# power.net
KiCad netlist of a schematic drawn in Altium Designer
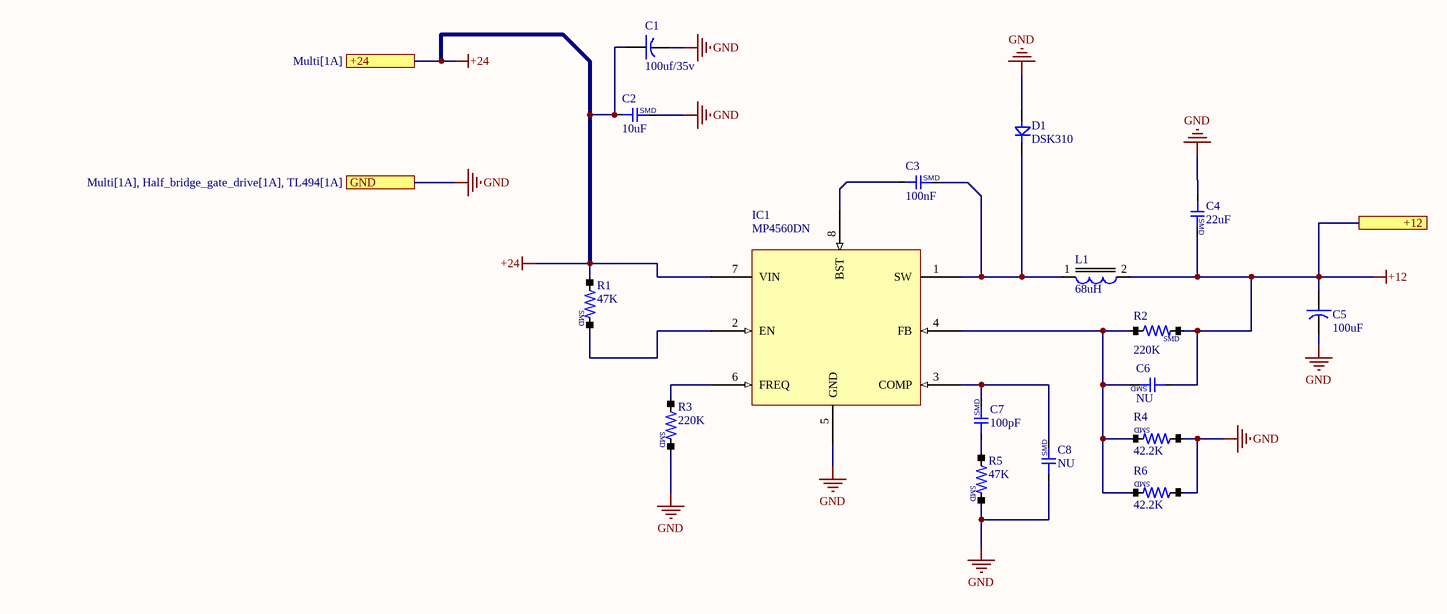
[diagram p0: power.SchDoc]

(export (version "E")
  (design (tool "Eeschema 10.0.6"))
  (components
    (comp (ref "C1")
      (value "100uf/35v")
      (footprint "cap/330u/16v")
      (libsource (lib "kave-eng-pro") (part "cap-electrolit"))
    )
    (comp (ref "C2") (value "10uF") (footprint "CAP-1206") (libsource (lib "kave-eng-pro") (part "cap_smd")))
    (comp (ref "C3") (value "100nF") (footprint "CAP-0603") (libsource (lib "kave-eng-pro") (part "cap_smd")))
    (comp (ref "C4") (value "22uF") (footprint "CAP-1206") (libsource (lib "kave-eng-pro") (part "cap_smd")))
    (comp (ref "C5")
      (value "100uF")
      (footprint "cap/330u/16v")
      (libsource (lib "kave-eng-pro") (part "cap-electrolit"))
    )
    (comp (ref "C6") (value "NU") (footprint "CAP-0603") (libsource (lib "kave-eng-pro") (part "cap_smd")))
    (comp (ref "C7") (value "100pF") (footprint "CAP-0603") (libsource (lib "kave-eng-pro") (part "cap_smd")))
    (comp (ref "C8") (value "NU") (footprint "CAP-0603") (libsource (lib "kave-eng-pro") (part "cap_smd")))
    (comp (ref "D1")
      (value "DSK310")
      (footprint "DIOD/1N4007/SMD")
      (libsource (lib "kave-eng-pro") (part "DIOD/RECTIFIERS"))
    )
    (comp (ref "IC1")
      (value "MP4560DN")
      (footprint "SOP8_HIT")
      (libsource (lib "kave-eng-pro") (part "MP4560DN"))
    )
    (comp (ref "L1")
      (value "68uH")
      (footprint "NR6028T680")
      (libsource (lib "kave-eng-pro") (part "inductor"))
    )
    (comp (ref "R1") (value "47K") (footprint "RES/0603") (libsource (lib "") (part "RES/SMD_1")))
    (comp (ref "R2") (value "220K") (footprint "RES/0603") (libsource (lib "") (part "RES/SMD_2")))
    (comp (ref "R3") (value "220K") (footprint "RES/0603") (libsource (lib "") (part "RES/SMD_1")))
    (comp (ref "R4") (value "42.2K") (footprint "RES/0603") (libsource (lib "kave-eng-pro") (part "RES/SMD")))
    (comp (ref "R5") (value "47K") (footprint "RES/0603") (libsource (lib "") (part "RES/SMD_1")))
    (comp (ref "R6") (value "42.2K") (footprint "RES/0603") (libsource (lib "kave-eng-pro") (part "RES/SMD")))
  )
  (nets
    (net (code "1") (name "+12") (class "Default")
      (node (ref "C4") (pin "2") (pintype "passive"))
      (node (ref "C5") (pin "+") (pintype "passive"))
      (node (ref "C6") (pin "1") (pintype "passive"))
      (node (ref "L1") (pin "2") (pintype "passive"))
      (node (ref "R2") (pin "2") (pinfunction "2_2") (pintype "passive"))
    )
    (net (code "2") (name "+24") (class "Default")
      (node (ref "C1") (pin "+") (pintype "passive"))
      (node (ref "C2") (pin "1") (pintype "passive"))
      (node (ref "IC1") (pin "7") (pinfunction "VIN_7") (pintype "power_in"))
      (node (ref "R1") (pin "1") (pinfunction "1_1") (pintype "passive"))
    )
    (net (code "3") (name "GND") (class "Default")
      (node (ref "C1") (pin "-") (pintype "passive"))
      (node (ref "C2") (pin "2") (pintype "passive"))
      (node (ref "C4") (pin "1") (pintype "passive"))
      (node (ref "C5") (pin "-") (pintype "passive"))
      (node (ref "C8") (pin "1") (pintype "passive"))
      (node (ref "D1") (pin "A") (pintype "passive"))
      (node (ref "IC1") (pin "5") (pinfunction "GND_5") (pintype "power_in"))
      (node (ref "R3") (pin "2") (pinfunction "2_2") (pintype "passive"))
      (node (ref "R4") (pin "1") (pinfunction "1_1") (pintype "passive"))
      (node (ref "R5") (pin "2") (pinfunction "2_2") (pintype "passive"))
      (node (ref "R6") (pin "1") (pinfunction "1_1") (pintype "passive"))
    )
    (net (code "4") (name "Net-(C7-Pad1)") (class "Default")
      (node (ref "C7") (pin "1") (pintype "passive"))
      (node (ref "R5") (pin "1") (pinfunction "1_1") (pintype "passive"))
    )
    (net (code "5") (name "Net-(IC1-BST)") (class "Default")
      (node (ref "C3") (pin "1") (pintype "passive"))
      (node (ref "IC1") (pin "8") (pinfunction "BST_8") (pintype "input"))
    )
    (net (code "6") (name "Net-(IC1-COMP)") (class "Default")
      (node (ref "C7") (pin "2") (pintype "passive"))
      (node (ref "C8") (pin "2") (pintype "passive"))
      (node (ref "IC1") (pin "3") (pinfunction "COMP_3") (pintype "input"))
    )
    (net (code "7") (name "Net-(IC1-EN)") (class "Default")
      (node (ref "IC1") (pin "2") (pinfunction "EN_2") (pintype "input"))
      (node (ref "R1") (pin "2") (pinfunction "2_2") (pintype "passive"))
    )
    (net (code "8") (name "Net-(IC1-FB)") (class "Default")
      (node (ref "C6") (pin "2") (pintype "passive"))
      (node (ref "IC1") (pin "4") (pinfunction "FB_4") (pintype "input"))
      (node (ref "R2") (pin "1") (pinfunction "1_1") (pintype "passive"))
      (node (ref "R4") (pin "2") (pinfunction "2_2") (pintype "passive"))
      (node (ref "R6") (pin "2") (pinfunction "2_2") (pintype "passive"))
    )
    (net (code "9") (name "Net-(IC1-FREQ)") (class "Default")
      (node (ref "IC1") (pin "6") (pinfunction "FREQ_6") (pintype "input"))
      (node (ref "R3") (pin "1") (pinfunction "1_1") (pintype "passive"))
    )
    (net (code "10") (name "Net-(IC1-SW)") (class "Default")
      (node (ref "C3") (pin "2") (pintype "passive"))
      (node (ref "D1") (pin "K") (pintype "passive"))
      (node (ref "IC1") (pin "1") (pinfunction "SW_1") (pintype "power_in"))
      (node (ref "L1") (pin "1") (pintype "passive"))
    )
  )
)
